# Protection_circuit.net
KiCad netlist of a schematic drawn in Altium Designer
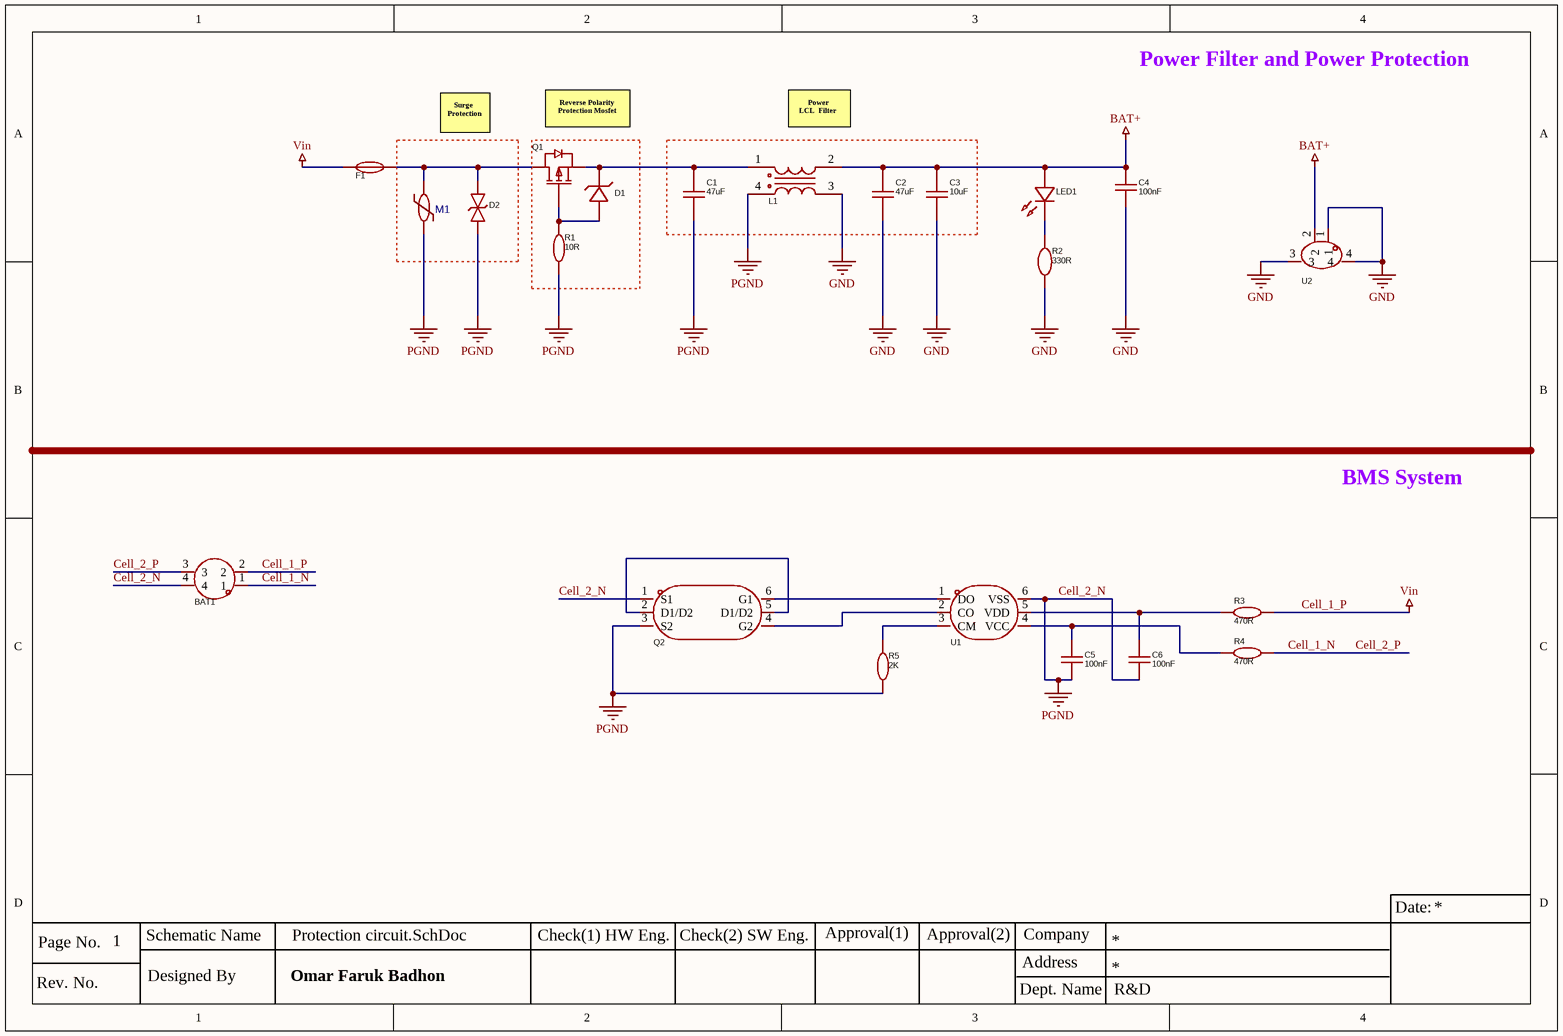
[diagram p0: Protection circuit.SchDoc]

(export (version "E")
  (design (tool "Eeschema 10.0.6"))
  (components
    (comp (ref "BAT1")
      (value "BH-18650-A1BJ021")
      (footprint "2 Cell Battery Case")
      (fields (field (name "MANUFACTURER") "MYOUNG(美阳)"))
      (libsource (lib "Battery circuit sch") (part "2 cell Battery Case"))
    )
    (comp (ref "C1")
      (value "47uF")
      (footprint "47uF Cap")
      (fields
        (field (name "MANUFACTURER") "IHHEC(禾伸堂)")
        (field (name "MANUFACTURER PART") "C1206B476M016T")
        (field (name "TOLERANCE") "±20%")
      )
      (libsource (lib "Battery circuit sch") (part "47uF Res"))
    )
    (comp (ref "C2")
      (value "47uF")
      (footprint "47uF Cap")
      (fields
        (field (name "MANUFACTURER") "IHHEC(禾伸堂)")
        (field (name "MANUFACTURER PART") "C1206B476M016T")
        (field (name "TOLERANCE") "±20%")
      )
      (libsource (lib "Battery circuit sch") (part "47uF Res"))
    )
    (comp (ref "C3")
      (value "10uF")
      (footprint "10uF Cap")
      (fields
        (field (name "MANUFACTURER") "muRata(村田)")
        (field (name "MANUFACTURER PART") "GRM32ER61C106KA12L")
        (field (name "TOLERANCE") "±10%")
      )
      (libsource (lib "Battery circuit sch") (part "10uF Cap"))
    )
    (comp (ref "C4")
      (value "100nF")
      (footprint "100nF Cap")
      (fields
        (field (name "MANUFACTURER") "muRata(村田)")
        (field (name "MANUFACTURER PART") "GRM188R71C104KA01D")
        (field (name "TOLERANCE") "±10%")
      )
      (libsource (lib "Battery circuit sch") (part "100nF Cap"))
    )
    (comp (ref "C5")
      (value "100nF")
      (footprint "100nF Cap")
      (fields
        (field (name "MANUFACTURER") "muRata(村田)")
        (field (name "MANUFACTURER PART") "GRM188R71C104KA01D")
        (field (name "TOLERANCE") "±10%")
      )
      (libsource (lib "Battery circuit sch") (part "100nF Cap"))
    )
    (comp (ref "C6")
      (value "100nF")
      (footprint "100nF Cap")
      (fields
        (field (name "MANUFACTURER") "muRata(村田)")
        (field (name "MANUFACTURER PART") "GRM188R71C104KA01D")
        (field (name "TOLERANCE") "±10%")
      )
      (libsource (lib "Battery circuit sch") (part "100nF Cap"))
    )
    (comp (ref "D1")
      (value "BZT52B6V8")
      (footprint "Zener Diode")
      (fields (field (name "MANUFACTURER") "FMS(美丽微)"))
      (libsource (lib "Battery circuit sch") (part "Zener Diode"))
    )
    (comp (ref "D2")
      (value "SDD32C24L01")
      (footprint "ESD Diode")
      (fields (field (name "MANUFACTURER") "Brightking(君耀电子)"))
      (libsource (lib "Battery circuit sch") (part "ESD Diode"))
    )
    (comp (ref "F1")
      (value "C05228-000")
      (footprint "Fuse_2")
      (fields (field (name "MANUFACTURER") "Littelfuse(美国力特)"))
      (libsource (lib "Battery circuit sch") (part "Fuse_2"))
    )
    (comp (ref "L1")
      (value "CMF4532F-900-2P-Tms")
      (footprint "CMC Filter")
      (fields (field (name "MANUFACTURER") "EMTEK(兆欣)"))
      (libsource (lib "Battery circuit sch") (part "CMC Filter"))
    )
    (comp (ref "LED1")
      (value "XL-1608SURC-06")
      (footprint "Led")
      (fields (field (name "MANUFACTURER") "XINGLIGHT(成兴光)"))
      (libsource (lib "Battery circuit sch") (part "Led"))
    )
    (comp (ref "M1")
      (value "EZJP0V270EA")
      (footprint "Varistor")
      (fields (field (name "MANUFACTURER") "PANASONIC(松下)") (field (name "CONTRIBUTOR") "LCSC"))
      (libsource (lib "Battery circuit sch") (part "Varistor"))
    )
    (comp (ref "Q1")
      (value "AO3401A")
      (footprint "P Mos")
      (fields (field (name "MANUFACTURER") "AOS"))
      (libsource (lib "Battery circuit sch") (part "P Mos"))
    )
    (comp (ref "Q2")
      (value "FS8205A")
      (footprint "2 N Mos")
      (fields (field (name "MANUFACTURER") "TECH PUBLIC(台舟)"))
      (libsource (lib "Battery circuit sch") (part "2 N Mos"))
    )
    (comp (ref "R1")
      (value "10R")
      (footprint "10R Res")
      (fields
        (field (name "MANUFACTURER") "FH(风华)")
        (field (name "MANUFACTURER PART") "RS-03K100JT")
        (field (name "TOLERANCE") "±5%")
      )
      (libsource (lib "Battery circuit sch") (part "10R Res"))
    )
    (comp (ref "R2")
      (value "330R")
      (footprint "330R Res")
      (fields
        (field (name "MANUFACTURER") "PANASONIC(松下)")
        (field (name "MANUFACTURER PART") "ERJPA2F3300X")
        (field (name "TOLERANCE") "±1%")
      )
      (libsource (lib "Battery circuit sch") (part "330R Res"))
    )
    (comp (ref "R3")
      (value "470R")
      (footprint "470R Res")
      (fields
        (field (name "MANUFACTURER") "LIZ(丽智电子)")
        (field (name "MANUFACTURER PART") "CR0402FF4700G")
        (field (name "TOLERANCE") "±1%")
      )
      (libsource (lib "Battery circuit sch") (part "470R Res"))
    )
    (comp (ref "R4")
      (value "470R")
      (footprint "470R Res")
      (fields
        (field (name "MANUFACTURER") "LIZ(丽智电子)")
        (field (name "MANUFACTURER PART") "CR0402FF4700G")
        (field (name "TOLERANCE") "±1%")
      )
      (libsource (lib "Battery circuit sch") (part "470R Res"))
    )
    (comp (ref "R5")
      (value "2K")
      (footprint "2K Res")
      (fields
        (field (name "MANUFACTURER") "FH(风华)")
        (field (name "MANUFACTURER PART") "RC-02W2001FT")
        (field (name "TOLERANCE") "±1%")
      )
      (libsource (lib "Battery circuit sch") (part "2K Res"))
    )
    (comp (ref "U1")
      (value "S-8252AAG-M6T1U")
      (footprint "BMS")
      (fields (field (name "MANUFACTURER") "ABLIC(艾普凌科)"))
      (libsource (lib "Battery circuit sch") (part "BMS"))
    )
    (comp (ref "U2")
      (value "BX-HA2.54-2PWT")
      (footprint "SMD JST 2P")
      (fields (field (name "MANUFACTURER") "Bossie(博锡)"))
      (libsource (lib "Battery circuit sch") (part "SMD JST"))
    )
  )
  (nets
    (net (code "1") (name "/Cell_1_N") (class "Default")
      (node (ref "BAT1") (pin "1") (pinfunction "1_1") (pintype "passive"))
      (node (ref "BAT1") (pin "3") (pinfunction "3_3") (pintype "passive"))
      (node (ref "R4") (pin "2") (pinfunction "2_2") (pintype "passive"))
    )
    (net (code "2") (name "BAT+") (class "Default")
      (node (ref "C2") (pin "2") (pinfunction "2_2") (pintype "passive"))
      (node (ref "C3") (pin "2") (pinfunction "2_2") (pintype "passive"))
      (node (ref "C4") (pin "2") (pinfunction "2_2") (pintype "passive"))
      (node (ref "L1") (pin "2") (pinfunction "2_2") (pintype "passive"))
      (node (ref "LED1") (pin "2") (pinfunction "A_2") (pintype "passive"))
      (node (ref "U2") (pin "2") (pinfunction "2_2") (pintype "passive"))
    )
    (net (code "3") (name "GND") (class "Default")
      (node (ref "C2") (pin "1") (pinfunction "1_1") (pintype "passive"))
      (node (ref "C3") (pin "1") (pinfunction "1_1") (pintype "passive"))
      (node (ref "C4") (pin "1") (pinfunction "1_1") (pintype "passive"))
      (node (ref "L1") (pin "3") (pinfunction "3_3") (pintype "passive"))
      (node (ref "R2") (pin "1") (pinfunction "1_1") (pintype "passive"))
      (node (ref "U2") (pin "1") (pinfunction "1_1") (pintype "passive"))
      (node (ref "U2") (pin "3") (pinfunction "3_3") (pintype "passive"))
      (node (ref "U2") (pin "4") (pinfunction "4_4") (pintype "passive"))
    )
    (net (code "4") (name "Net-(D1-A)") (class "Default")
      (node (ref "D1") (pin "2") (pinfunction "A_2") (pintype "passive"))
      (node (ref "Q1") (pin "1") (pinfunction "G_1") (pintype "passive"))
      (node (ref "R1") (pin "2") (pinfunction "2_2") (pintype "passive"))
    )
    (net (code "5") (name "Net-(D1-K)") (class "Default")
      (node (ref "C1") (pin "2") (pinfunction "2_2") (pintype "passive"))
      (node (ref "D1") (pin "1") (pinfunction "K_1") (pintype "passive"))
      (node (ref "L1") (pin "1") (pinfunction "1_1") (pintype "passive"))
      (node (ref "Q1") (pin "2") (pinfunction "S_2") (pintype "passive"))
    )
    (net (code "6") (name "Net-(LED1-K)") (class "Default")
      (node (ref "LED1") (pin "1") (pinfunction "K_1") (pintype "passive"))
      (node (ref "R2") (pin "2") (pinfunction "2_2") (pintype "passive"))
    )
    (net (code "7") (name "Net-(Q1-D)") (class "Default")
      (node (ref "D2") (pin "2") (pinfunction "2_2") (pintype "passive"))
      (node (ref "F1") (pin "2") (pinfunction "2_2") (pintype "passive"))
      (node (ref "M1") (pin "2") (pinfunction "2_2") (pintype "passive"))
      (node (ref "Q1") (pin "3") (pinfunction "D_3") (pintype "passive"))
    )
    (net (code "8") (name "Net-(Q2-D1{slash}D2-Pad2)") (class "Default")
      (node (ref "Q2") (pin "2") (pinfunction "D1/D2_2") (pintype "passive"))
      (node (ref "Q2") (pin "5") (pinfunction "D1/D2_5") (pintype "passive"))
    )
    (net (code "9") (name "Net-(Q2-G1)") (class "Default")
      (node (ref "Q2") (pin "6") (pinfunction "G1_6") (pintype "passive"))
      (node (ref "U1") (pin "1") (pinfunction "DO_1") (pintype "passive"))
    )
    (net (code "10") (name "Net-(Q2-G2)") (class "Default")
      (node (ref "Q2") (pin "4") (pinfunction "G2_4") (pintype "passive"))
      (node (ref "U1") (pin "2") (pinfunction "CO_2") (pintype "passive"))
    )
    (net (code "11") (name "Net-(U1-CM)") (class "Default")
      (node (ref "R5") (pin "2") (pinfunction "2_2") (pintype "passive"))
      (node (ref "U1") (pin "3") (pinfunction "CM_3") (pintype "passive"))
    )
    (net (code "12") (name "Net-(U1-VCC)") (class "Default")
      (node (ref "C5") (pin "2") (pinfunction "2_2") (pintype "passive"))
      (node (ref "R4") (pin "1") (pinfunction "1_1") (pintype "passive"))
      (node (ref "U1") (pin "4") (pinfunction "VCC_4") (pintype "passive"))
    )
    (net (code "13") (name "Net-(U1-VDD)") (class "Default")
      (node (ref "C6") (pin "2") (pinfunction "2_2") (pintype "passive"))
      (node (ref "R3") (pin "1") (pinfunction "1_1") (pintype "passive"))
      (node (ref "U1") (pin "5") (pinfunction "VDD_5") (pintype "passive"))
    )
    (net (code "14") (name "PGND") (class "Default")
      (node (ref "BAT1") (pin "4") (pinfunction "4_4") (pintype "passive"))
      (node (ref "C1") (pin "1") (pinfunction "1_1") (pintype "passive"))
      (node (ref "C5") (pin "1") (pinfunction "1_1") (pintype "passive"))
      (node (ref "C6") (pin "1") (pinfunction "1_1") (pintype "passive"))
      (node (ref "D2") (pin "1") (pinfunction "1_1") (pintype "passive"))
      (node (ref "L1") (pin "4") (pinfunction "4_4") (pintype "passive"))
      (node (ref "M1") (pin "1") (pinfunction "1_1") (pintype "passive"))
      (node (ref "Q2") (pin "1") (pinfunction "S1_1") (pintype "passive"))
      (node (ref "Q2") (pin "3") (pinfunction "S2_3") (pintype "passive"))
      (node (ref "R1") (pin "1") (pinfunction "1_1") (pintype "passive"))
      (node (ref "R5") (pin "1") (pinfunction "1_1") (pintype "passive"))
      (node (ref "U1") (pin "6") (pinfunction "VSS_6") (pintype "passive"))
    )
    (net (code "15") (name "Vin") (class "Default")
      (node (ref "BAT1") (pin "2") (pinfunction "2_2") (pintype "passive"))
      (node (ref "F1") (pin "1") (pinfunction "1_1") (pintype "passive"))
      (node (ref "R3") (pin "2") (pinfunction "2_2") (pintype "passive"))
    )
  )
)
